# B4L_UI.net
KiCad netlist of a schematic drawn in EAGLE
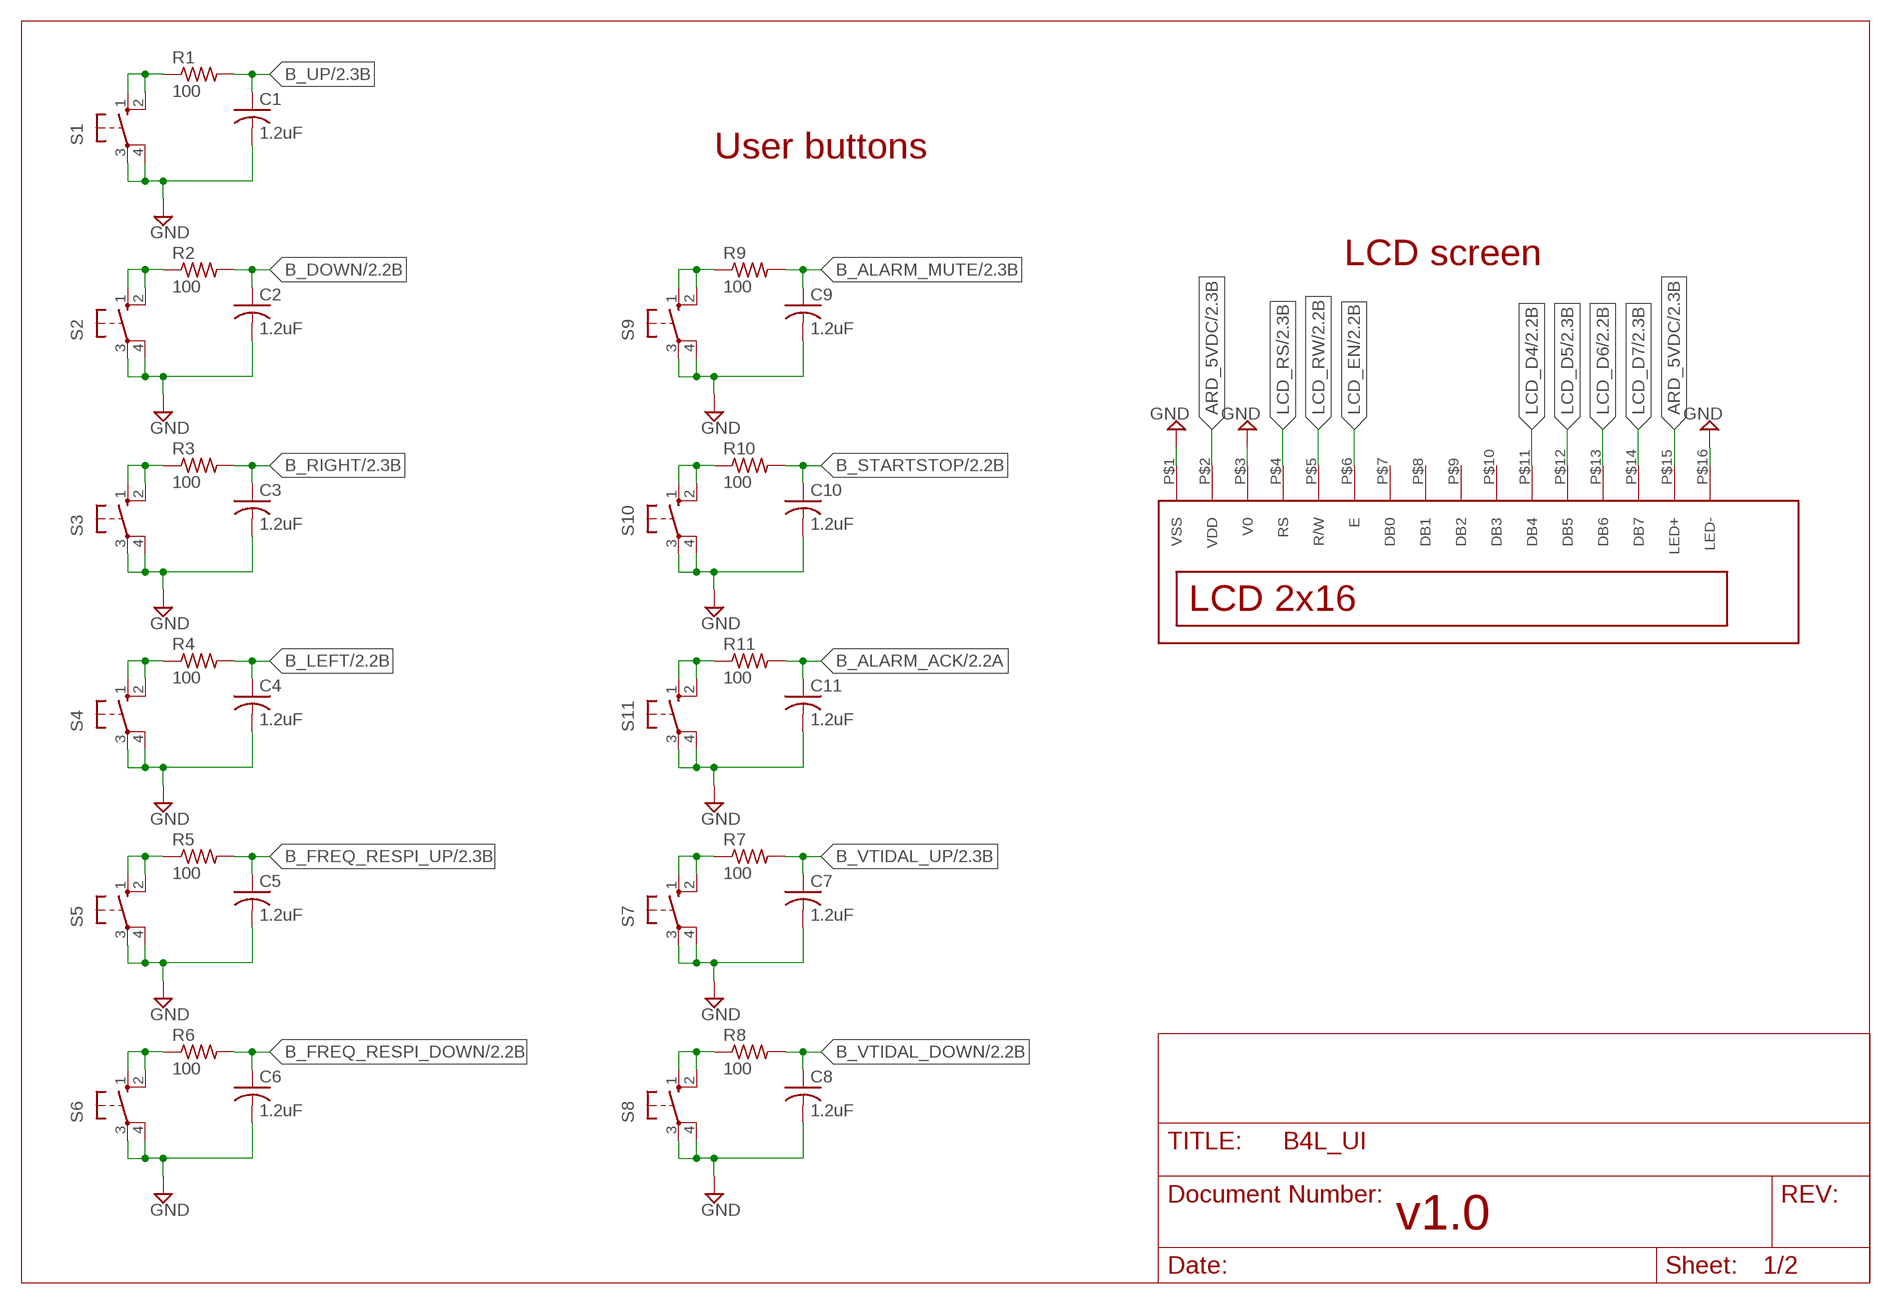
[diagram p0: schematic, sheet 1]
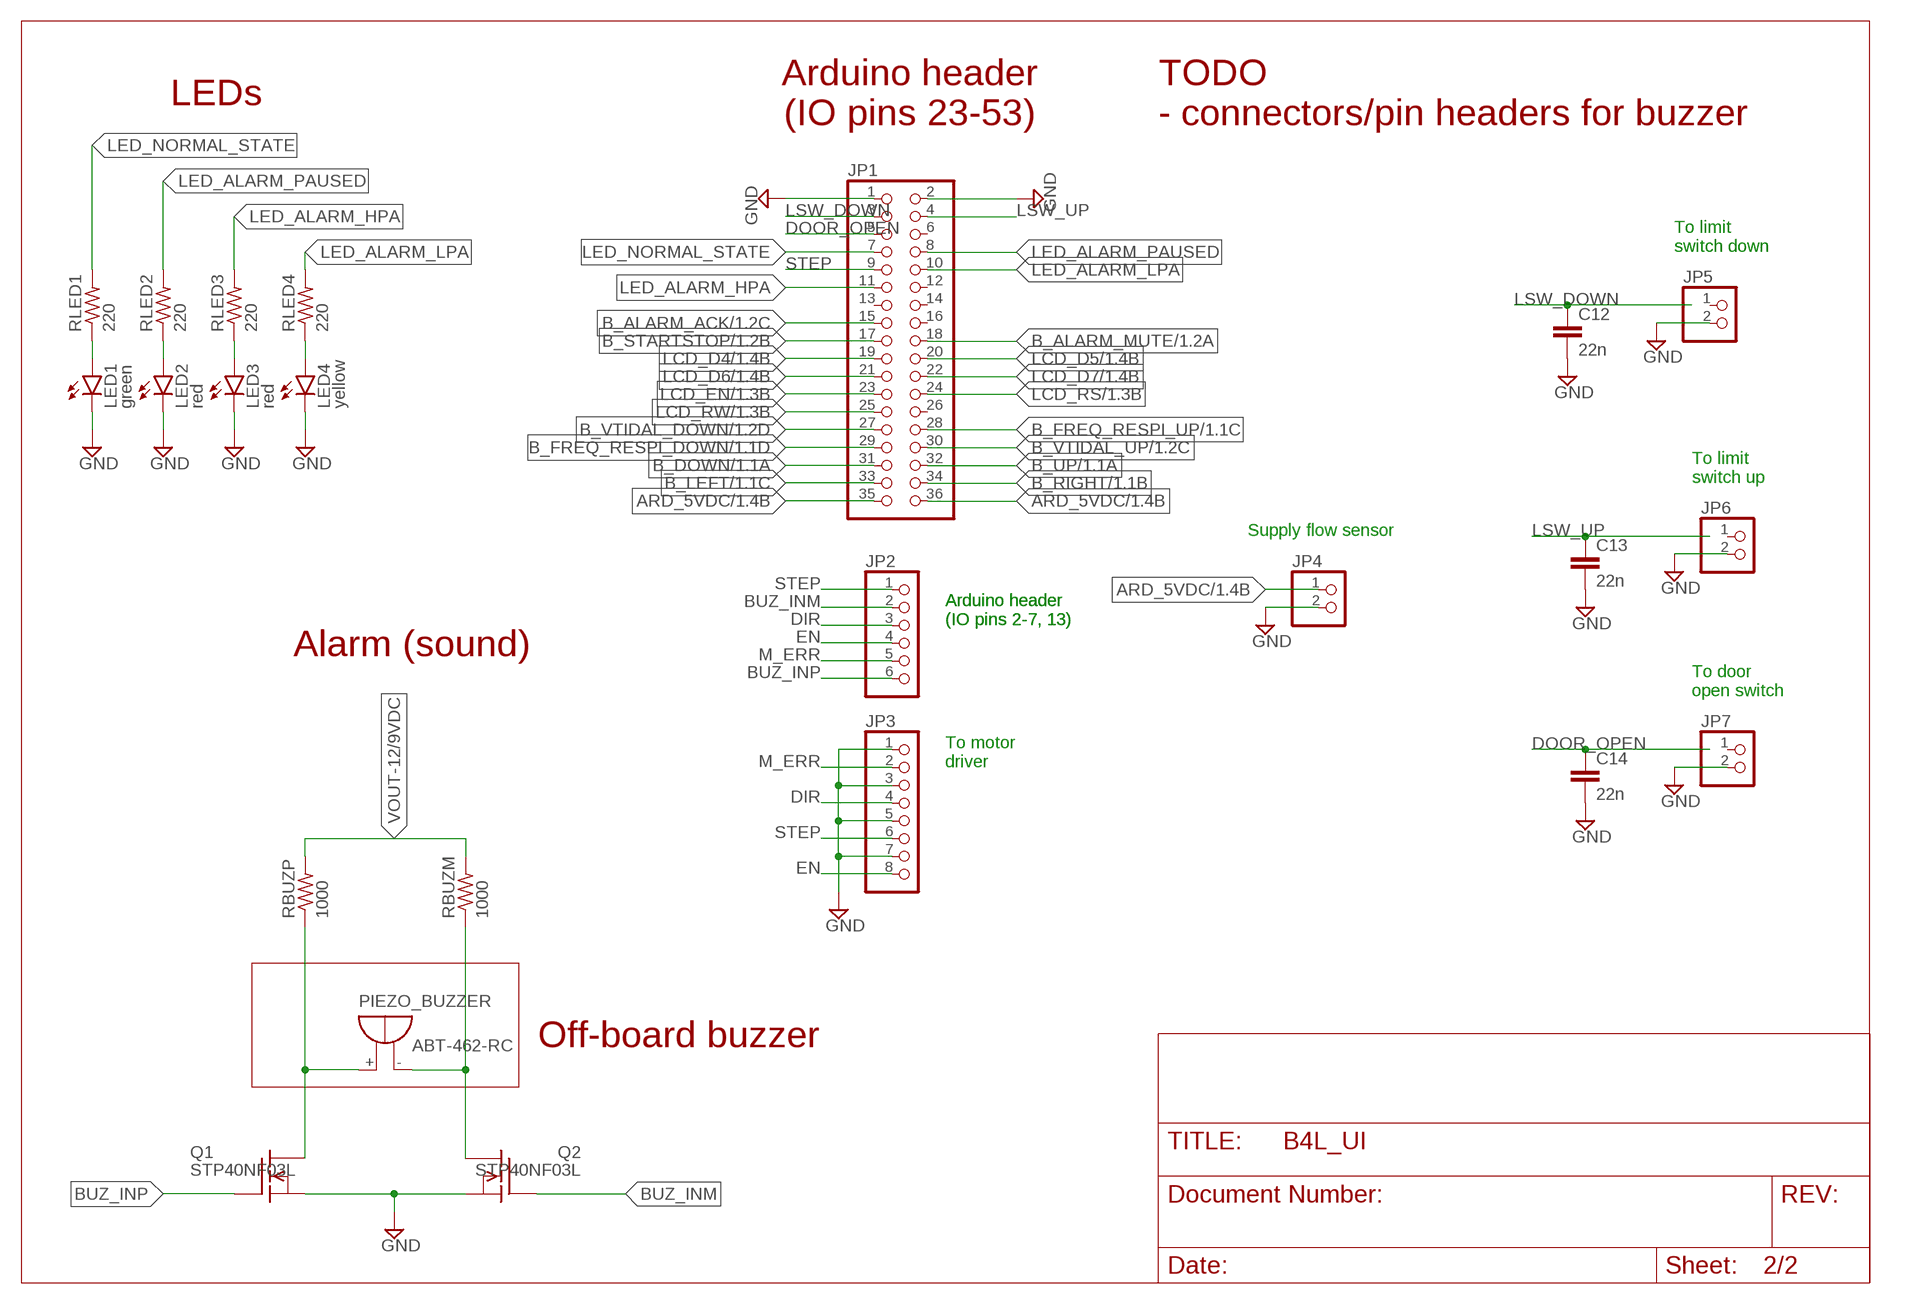
[diagram p1: schematic, sheet 2]

(export (version "E")
  (design (tool "Eeschema 10.0.6"))
  (components
    (comp (ref "C1")
      (value "1.2uF")
      (footprint "eagle-import:C050-050X075")
      (libsource (lib "eagle-import") (part "C-US050-050X075"))
    )
    (comp (ref "C2")
      (value "1.2uF")
      (footprint "eagle-import:C050-050X075")
      (libsource (lib "eagle-import") (part "C-US050-050X075"))
    )
    (comp (ref "C3")
      (value "1.2uF")
      (footprint "eagle-import:C050-050X075")
      (libsource (lib "eagle-import") (part "C-US050-050X075"))
    )
    (comp (ref "C4")
      (value "1.2uF")
      (footprint "eagle-import:C050-050X075")
      (libsource (lib "eagle-import") (part "C-US050-050X075"))
    )
    (comp (ref "C5")
      (value "1.2uF")
      (footprint "eagle-import:C050-050X075")
      (libsource (lib "eagle-import") (part "C-US050-050X075"))
    )
    (comp (ref "C6")
      (value "1.2uF")
      (footprint "eagle-import:C050-050X075")
      (libsource (lib "eagle-import") (part "C-US050-050X075"))
    )
    (comp (ref "C7")
      (value "1.2uF")
      (footprint "eagle-import:C050-050X075")
      (libsource (lib "eagle-import") (part "C-US050-050X075"))
    )
    (comp (ref "C8")
      (value "1.2uF")
      (footprint "eagle-import:C050-050X075")
      (libsource (lib "eagle-import") (part "C-US050-050X075"))
    )
    (comp (ref "C9")
      (value "1.2uF")
      (footprint "eagle-import:C050-050X075")
      (libsource (lib "eagle-import") (part "C-US050-050X075"))
    )
    (comp (ref "C10")
      (value "1.2uF")
      (footprint "eagle-import:C050-050X075")
      (libsource (lib "eagle-import") (part "C-US050-050X075"))
    )
    (comp (ref "C11")
      (value "1.2uF")
      (footprint "eagle-import:C050-050X075")
      (libsource (lib "eagle-import") (part "C-US050-050X075"))
    )
    (comp (ref "R1")
      (value "100")
      (footprint "eagle-import:0309_12")
      (libsource (lib "eagle-import") (part "R-US_0309/12"))
    )
    (comp (ref "R2")
      (value "100")
      (footprint "eagle-import:0309_12")
      (libsource (lib "eagle-import") (part "R-US_0309/12"))
    )
    (comp (ref "R3")
      (value "100")
      (footprint "eagle-import:0309_12")
      (libsource (lib "eagle-import") (part "R-US_0309/12"))
    )
    (comp (ref "R4")
      (value "100")
      (footprint "eagle-import:0309_12")
      (libsource (lib "eagle-import") (part "R-US_0309/12"))
    )
    (comp (ref "R5")
      (value "100")
      (footprint "eagle-import:0309_12")
      (libsource (lib "eagle-import") (part "R-US_0309/12"))
    )
    (comp (ref "R6")
      (value "100")
      (footprint "eagle-import:0309_12")
      (libsource (lib "eagle-import") (part "R-US_0309/12"))
    )
    (comp (ref "R7")
      (value "100")
      (footprint "eagle-import:0309_12")
      (libsource (lib "eagle-import") (part "R-US_0309/12"))
    )
    (comp (ref "R8")
      (value "100")
      (footprint "eagle-import:0309_12")
      (libsource (lib "eagle-import") (part "R-US_0309/12"))
    )
    (comp (ref "R9")
      (value "100")
      (footprint "eagle-import:0309_12")
      (libsource (lib "eagle-import") (part "R-US_0309/12"))
    )
    (comp (ref "R10")
      (value "100")
      (footprint "eagle-import:0309_12")
      (libsource (lib "eagle-import") (part "R-US_0309/12"))
    )
    (comp (ref "R11")
      (value "100")
      (footprint "eagle-import:0309_12")
      (libsource (lib "eagle-import") (part "R-US_0309/12"))
    )
    (comp (ref "S1")
      (value "40-XX")
      (footprint "eagle-import:B3F-40XX")
      (fields (field (name "MF") "OMRON COMPONENTS USA") (field (name "MPN") "B3F-4000"))
      (libsource (lib "eagle-import") (part "40-XX"))
    )
    (comp (ref "S2")
      (value "40-XX")
      (footprint "eagle-import:B3F-40XX")
      (fields (field (name "MF") "OMRON COMPONENTS USA") (field (name "MPN") "B3F-4000"))
      (libsource (lib "eagle-import") (part "40-XX"))
    )
    (comp (ref "S3")
      (value "40-XX")
      (footprint "eagle-import:B3F-40XX")
      (fields (field (name "MF") "OMRON COMPONENTS USA") (field (name "MPN") "B3F-4000"))
      (libsource (lib "eagle-import") (part "40-XX"))
    )
    (comp (ref "S4")
      (value "40-XX")
      (footprint "eagle-import:B3F-40XX")
      (fields (field (name "MF") "OMRON COMPONENTS USA") (field (name "MPN") "B3F-4000"))
      (libsource (lib "eagle-import") (part "40-XX"))
    )
    (comp (ref "S5")
      (value "40-XX")
      (footprint "eagle-import:B3F-40XX")
      (fields (field (name "MF") "OMRON COMPONENTS USA") (field (name "MPN") "B3F-4000"))
      (libsource (lib "eagle-import") (part "40-XX"))
    )
    (comp (ref "S6")
      (value "40-XX")
      (footprint "eagle-import:B3F-40XX")
      (fields (field (name "MF") "OMRON COMPONENTS USA") (field (name "MPN") "B3F-4000"))
      (libsource (lib "eagle-import") (part "40-XX"))
    )
    (comp (ref "S7")
      (value "40-XX")
      (footprint "eagle-import:B3F-40XX")
      (fields (field (name "MF") "OMRON COMPONENTS USA") (field (name "MPN") "B3F-4000"))
      (libsource (lib "eagle-import") (part "40-XX"))
    )
    (comp (ref "S8")
      (value "40-XX")
      (footprint "eagle-import:B3F-40XX")
      (fields (field (name "MF") "OMRON COMPONENTS USA") (field (name "MPN") "B3F-4000"))
      (libsource (lib "eagle-import") (part "40-XX"))
    )
    (comp (ref "S9")
      (value "40-XX")
      (footprint "eagle-import:B3F-40XX")
      (fields (field (name "MF") "OMRON COMPONENTS USA") (field (name "MPN") "B3F-4000"))
      (libsource (lib "eagle-import") (part "40-XX"))
    )
    (comp (ref "S10")
      (value "40-XX")
      (footprint "eagle-import:B3F-40XX")
      (fields (field (name "MF") "OMRON COMPONENTS USA") (field (name "MPN") "B3F-4000"))
      (libsource (lib "eagle-import") (part "40-XX"))
    )
    (comp (ref "S11")
      (value "40-XX")
      (footprint "eagle-import:B3F-40XX")
      (fields (field (name "MF") "OMRON COMPONENTS USA") (field (name "MPN") "B3F-4000"))
      (libsource (lib "eagle-import") (part "40-XX"))
    )
    (comp (ref "U$1")
      (value "LCD_MC21605C6W-BNMLW-V2")
      (footprint "eagle-import:LCD_MC21605C6W-BNMLW-V2")
      (libsource (lib "eagle-import") (part "LCD_MC21605C6W-BNMLW-V2"))
    )
    (comp (ref "C12")
      (value "22n")
      (footprint "eagle-import:C2.5-3")
      (libsource (lib "eagle-import") (part "C2,5-3"))
    )
    (comp (ref "C13")
      (value "22n")
      (footprint "eagle-import:C2.5-3")
      (libsource (lib "eagle-import") (part "C2,5-3"))
    )
    (comp (ref "C14")
      (value "22n")
      (footprint "eagle-import:C2.5-3")
      (libsource (lib "eagle-import") (part "C2,5-3"))
    )
    (comp (ref "JP1")
      (value "PINHD-2X18")
      (footprint "eagle-import:2X18")
      (libsource (lib "eagle-import") (part "PINHD-2X18"))
    )
    (comp (ref "JP2")
      (value "PINHD-1X6")
      (footprint "eagle-import:1X06")
      (libsource (lib "eagle-import") (part "PINHD-1X6"))
    )
    (comp (ref "JP3")
      (value "PINHD-1X8")
      (footprint "eagle-import:1X08")
      (libsource (lib "eagle-import") (part "PINHD-1X8"))
    )
    (comp (ref "JP4")
      (value "PINHD-1X2")
      (footprint "eagle-import:1X02")
      (libsource (lib "eagle-import") (part "PINHD-1X2"))
    )
    (comp (ref "JP5")
      (value "PINHD-1X2")
      (footprint "eagle-import:1X02")
      (libsource (lib "eagle-import") (part "PINHD-1X2"))
    )
    (comp (ref "JP6")
      (value "PINHD-1X2")
      (footprint "eagle-import:1X02")
      (libsource (lib "eagle-import") (part "PINHD-1X2"))
    )
    (comp (ref "JP7")
      (value "PINHD-1X2")
      (footprint "eagle-import:1X02")
      (libsource (lib "eagle-import") (part "PINHD-1X2"))
    )
    (comp (ref "LED1")
      (value "green")
      (footprint "eagle-import:LED5MM")
      (libsource (lib "eagle-import") (part "LED5MM"))
    )
    (comp (ref "LED2")
      (value "red")
      (footprint "eagle-import:LED5MM")
      (libsource (lib "eagle-import") (part "LED5MM"))
    )
    (comp (ref "LED3")
      (value "red")
      (footprint "eagle-import:LED5MM")
      (libsource (lib "eagle-import") (part "LED5MM"))
    )
    (comp (ref "LED4")
      (value "yellow")
      (footprint "eagle-import:LED5MM")
      (libsource (lib "eagle-import") (part "LED5MM"))
    )
    (comp (ref "PIEZO_BUZZER")
      (value "ABT-462-RC")
      (footprint "eagle-import:F_TMB")
      (libsource (lib "eagle-import") (part "F/TMB"))
    )
    (comp (ref "Q1")
      (value "STP40NF03L")
      (footprint "eagle-import:TO220")
      (libsource (lib "eagle-import") (part "BUZ10"))
    )
    (comp (ref "Q2")
      (value "STP40NF03L")
      (footprint "eagle-import:TO220")
      (libsource (lib "eagle-import") (part "BUZ10"))
    )
    (comp (ref "RBUZM")
      (value "1000")
      (footprint "eagle-import:0309_12")
      (libsource (lib "eagle-import") (part "R-US_0309/12"))
    )
    (comp (ref "RBUZP")
      (value "1000")
      (footprint "eagle-import:0309_12")
      (libsource (lib "eagle-import") (part "R-US_0309/12"))
    )
    (comp (ref "RLED1")
      (value "220")
      (footprint "eagle-import:0309_12")
      (libsource (lib "eagle-import") (part "R-US_0309/12"))
    )
    (comp (ref "RLED2")
      (value "220")
      (footprint "eagle-import:0309_12")
      (libsource (lib "eagle-import") (part "R-US_0309/12"))
    )
    (comp (ref "RLED3")
      (value "220")
      (footprint "eagle-import:0309_12")
      (libsource (lib "eagle-import") (part "R-US_0309/12"))
    )
    (comp (ref "RLED4")
      (value "220")
      (footprint "eagle-import:0309_12")
      (libsource (lib "eagle-import") (part "R-US_0309/12"))
    )
  )
  (nets
    (net (code "1") (name "ARD_5VDC") (class "Default")
      (node (ref "JP1") (pin "35") (pinfunction "35_35") (pintype "passive"))
      (node (ref "JP1") (pin "36") (pinfunction "36_36") (pintype "passive"))
      (node (ref "U$1") (pin "P$15") (pinfunction "LED+_P$15") (pintype "bidirectional"))
      (node (ref "U$1") (pin "P$2") (pinfunction "VDD_P$2") (pintype "bidirectional"))
    )
    (net (code "2") (name "BUZ_INM") (class "Default")
      (node (ref "JP2") (pin "2") (pinfunction "2_2") (pintype "passive"))
      (node (ref "Q2") (pin "1") (pinfunction "G_1") (pintype "passive"))
    )
    (net (code "3") (name "BUZ_INP") (class "Default")
      (node (ref "JP2") (pin "6") (pinfunction "6_6") (pintype "passive"))
      (node (ref "Q1") (pin "1") (pinfunction "G_1") (pintype "passive"))
    )
    (net (code "4") (name "B_ALARM_ACK") (class "Default")
      (node (ref "C11") (pin "1") (pinfunction "1_1") (pintype "passive"))
      (node (ref "JP1") (pin "15") (pinfunction "15_15") (pintype "passive"))
      (node (ref "R11") (pin "2") (pinfunction "2_2") (pintype "passive"))
    )
    (net (code "5") (name "B_ALARM_MUTE") (class "Default")
      (node (ref "C9") (pin "1") (pinfunction "1_1") (pintype "passive"))
      (node (ref "JP1") (pin "18") (pinfunction "18_18") (pintype "passive"))
      (node (ref "R9") (pin "2") (pinfunction "2_2") (pintype "passive"))
    )
    (net (code "6") (name "B_DOWN") (class "Default")
      (node (ref "C2") (pin "1") (pinfunction "1_1") (pintype "passive"))
      (node (ref "JP1") (pin "31") (pinfunction "31_31") (pintype "passive"))
      (node (ref "R2") (pin "2") (pinfunction "2_2") (pintype "passive"))
    )
    (net (code "7") (name "B_FREQ_RESPI_DOWN") (class "Default")
      (node (ref "C6") (pin "1") (pinfunction "1_1") (pintype "passive"))
      (node (ref "JP1") (pin "29") (pinfunction "29_29") (pintype "passive"))
      (node (ref "R6") (pin "2") (pinfunction "2_2") (pintype "passive"))
    )
    (net (code "8") (name "B_FREQ_RESPI_UP") (class "Default")
      (node (ref "C5") (pin "1") (pinfunction "1_1") (pintype "passive"))
      (node (ref "JP1") (pin "28") (pinfunction "28_28") (pintype "passive"))
      (node (ref "R5") (pin "2") (pinfunction "2_2") (pintype "passive"))
    )
    (net (code "9") (name "B_LEFT") (class "Default")
      (node (ref "C4") (pin "1") (pinfunction "1_1") (pintype "passive"))
      (node (ref "JP1") (pin "33") (pinfunction "33_33") (pintype "passive"))
      (node (ref "R4") (pin "2") (pinfunction "2_2") (pintype "passive"))
    )
    (net (code "10") (name "B_RIGHT") (class "Default")
      (node (ref "C3") (pin "1") (pinfunction "1_1") (pintype "passive"))
      (node (ref "JP1") (pin "34") (pinfunction "34_34") (pintype "passive"))
      (node (ref "R3") (pin "2") (pinfunction "2_2") (pintype "passive"))
    )
    (net (code "11") (name "B_STARTSTOP") (class "Default")
      (node (ref "C10") (pin "1") (pinfunction "1_1") (pintype "passive"))
      (node (ref "JP1") (pin "17") (pinfunction "17_17") (pintype "passive"))
      (node (ref "R10") (pin "2") (pinfunction "2_2") (pintype "passive"))
    )
    (net (code "12") (name "B_UP") (class "Default")
      (node (ref "C1") (pin "1") (pinfunction "1_1") (pintype "passive"))
      (node (ref "JP1") (pin "32") (pinfunction "32_32") (pintype "passive"))
      (node (ref "R1") (pin "2") (pinfunction "2_2") (pintype "passive"))
    )
    (net (code "13") (name "B_VTIDAL_DOWN") (class "Default")
      (node (ref "C8") (pin "1") (pinfunction "1_1") (pintype "passive"))
      (node (ref "JP1") (pin "27") (pinfunction "27_27") (pintype "passive"))
      (node (ref "R8") (pin "2") (pinfunction "2_2") (pintype "passive"))
    )
    (net (code "14") (name "B_VTIDAL_UP") (class "Default")
      (node (ref "C7") (pin "1") (pinfunction "1_1") (pintype "passive"))
      (node (ref "JP1") (pin "30") (pinfunction "30_30") (pintype "passive"))
      (node (ref "R7") (pin "2") (pinfunction "2_2") (pintype "passive"))
    )
    (net (code "15") (name "DIR") (class "Default")
      (node (ref "JP2") (pin "3") (pinfunction "3_3") (pintype "passive"))
      (node (ref "JP3") (pin "4") (pinfunction "4_4") (pintype "passive"))
    )
    (net (code "16") (name "DOOR_OPEN") (class "Default")
      (node (ref "C14") (pin "1") (pinfunction "1_1") (pintype "passive"))
      (node (ref "JP1") (pin "5") (pinfunction "5_5") (pintype "passive"))
    )
    (net (code "17") (name "EN") (class "Default")
      (node (ref "JP2") (pin "4") (pinfunction "4_4") (pintype "passive"))
      (node (ref "JP3") (pin "8") (pinfunction "8_8") (pintype "passive"))
    )
    (net (code "18") (name "GND") (class "Default")
      (node (ref "C1") (pin "2") (pinfunction "2_2") (pintype "passive"))
      (node (ref "C10") (pin "2") (pinfunction "2_2") (pintype "passive"))
      (node (ref "C11") (pin "2") (pinfunction "2_2") (pintype "passive"))
      (node (ref "C12") (pin "2") (pinfunction "2_2") (pintype "passive"))
      (node (ref "C13") (pin "2") (pinfunction "2_2") (pintype "passive"))
      (node (ref "C14") (pin "2") (pinfunction "2_2") (pintype "passive"))
      (node (ref "C2") (pin "2") (pinfunction "2_2") (pintype "passive"))
      (node (ref "C3") (pin "2") (pinfunction "2_2") (pintype "passive"))
      (node (ref "C4") (pin "2") (pinfunction "2_2") (pintype "passive"))
      (node (ref "C5") (pin "2") (pinfunction "2_2") (pintype "passive"))
      (node (ref "C6") (pin "2") (pinfunction "2_2") (pintype "passive"))
      (node (ref "C7") (pin "2") (pinfunction "2_2") (pintype "passive"))
      (node (ref "C8") (pin "2") (pinfunction "2_2") (pintype "passive"))
      (node (ref "C9") (pin "2") (pinfunction "2_2") (pintype "passive"))
      (node (ref "JP1") (pin "1") (pinfunction "1_1") (pintype "passive"))
      (node (ref "JP1") (pin "2") (pinfunction "2_2") (pintype "passive"))
      (node (ref "JP3") (pin "1") (pinfunction "1_1") (pintype "passive"))
      (node (ref "JP3") (pin "3") (pinfunction "3_3") (pintype "passive"))
      (node (ref "JP3") (pin "5") (pinfunction "5_5") (pintype "passive"))
      (node (ref "JP3") (pin "7") (pinfunction "7_7") (pintype "passive"))
      (node (ref "JP4") (pin "2") (pinfunction "2_2") (pintype "passive"))
      (node (ref "JP5") (pin "2") (pinfunction "2_2") (pintype "passive"))
      (node (ref "JP6") (pin "2") (pinfunction "2_2") (pintype "passive"))
      (node (ref "JP7") (pin "2") (pinfunction "2_2") (pintype "passive"))
      (node (ref "LED1") (pin "K") (pinfunction "C_K") (pintype "passive"))
      (node (ref "LED2") (pin "K") (pinfunction "C_K") (pintype "passive"))
      (node (ref "LED3") (pin "K") (pinfunction "C_K") (pintype "passive"))
      (node (ref "LED4") (pin "K") (pinfunction "C_K") (pintype "passive"))
      (node (ref "Q1") (pin "3") (pinfunction "S_3") (pintype "passive"))
      (node (ref "Q2") (pin "3") (pinfunction "S_3") (pintype "passive"))
      (node (ref "S1") (pin "3") (pinfunction "P_3") (pintype "passive"))
      (node (ref "S1") (pin "4") (pinfunction "P1_4") (pintype "passive"))
      (node (ref "S10") (pin "3") (pinfunction "P_3") (pintype "passive"))
      (node (ref "S10") (pin "4") (pinfunction "P1_4") (pintype "passive"))
      (node (ref "S11") (pin "3") (pinfunction "P_3") (pintype "passive"))
      (node (ref "S11") (pin "4") (pinfunction "P1_4") (pintype "passive"))
      (node (ref "S2") (pin "3") (pinfunction "P_3") (pintype "passive"))
      (node (ref "S2") (pin "4") (pinfunction "P1_4") (pintype "passive"))
      (node (ref "S3") (pin "3") (pinfunction "P_3") (pintype "passive"))
      (node (ref "S3") (pin "4") (pinfunction "P1_4") (pintype "passive"))
      (node (ref "S4") (pin "3") (pinfunction "P_3") (pintype "passive"))
      (node (ref "S4") (pin "4") (pinfunction "P1_4") (pintype "passive"))
      (node (ref "S5") (pin "3") (pinfunction "P_3") (pintype "passive"))
      (node (ref "S5") (pin "4") (pinfunction "P1_4") (pintype "passive"))
      (node (ref "S6") (pin "3") (pinfunction "P_3") (pintype "passive"))
      (node (ref "S6") (pin "4") (pinfunction "P1_4") (pintype "passive"))
      (node (ref "S7") (pin "3") (pinfunction "P_3") (pintype "passive"))
      (node (ref "S7") (pin "4") (pinfunction "P1_4") (pintype "passive"))
      (node (ref "S8") (pin "3") (pinfunction "P_3") (pintype "passive"))
      (node (ref "S8") (pin "4") (pinfunction "P1_4") (pintype "passive"))
      (node (ref "S9") (pin "3") (pinfunction "P_3") (pintype "passive"))
      (node (ref "S9") (pin "4") (pinfunction "P1_4") (pintype "passive"))
      (node (ref "U$1") (pin "P$1") (pinfunction "VSS_P$1") (pintype "bidirectional"))
      (node (ref "U$1") (pin "P$16") (pinfunction "LED-_P$16") (pintype "bidirectional"))
      (node (ref "U$1") (pin "P$3") (pinfunction "V0_P$3") (pintype "bidirectional"))
    )
    (net (code "19") (name "LCD_D4") (class "Default")
      (node (ref "JP1") (pin "19") (pinfunction "19_19") (pintype "passive"))
      (node (ref "U$1") (pin "P$11") (pinfunction "DB4_P$11") (pintype "bidirectional"))
    )
    (net (code "20") (name "LCD_D5") (class "Default")
      (node (ref "JP1") (pin "20") (pinfunction "20_20") (pintype "passive"))
      (node (ref "U$1") (pin "P$12") (pinfunction "DB5_P$12") (pintype "bidirectional"))
    )
    (net (code "21") (name "LCD_D6") (class "Default")
      (node (ref "JP1") (pin "21") (pinfunction "21_21") (pintype "passive"))
      (node (ref "U$1") (pin "P$13") (pinfunction "DB6_P$13") (pintype "bidirectional"))
    )
    (net (code "22") (name "LCD_D7") (class "Default")
      (node (ref "JP1") (pin "22") (pinfunction "22_22") (pintype "passive"))
      (node (ref "U$1") (pin "P$14") (pinfunction "DB7_P$14") (pintype "bidirectional"))
    )
    (net (code "23") (name "LCD_EN") (class "Default")
      (node (ref "JP1") (pin "23") (pinfunction "23_23") (pintype "passive"))
      (node (ref "U$1") (pin "P$6") (pinfunction "E_P$6") (pintype "bidirectional"))
    )
    (net (code "24") (name "LCD_RS") (class "Default")
      (node (ref "JP1") (pin "24") (pinfunction "24_24") (pintype "passive"))
      (node (ref "U$1") (pin "P$4") (pinfunction "RS_P$4") (pintype "bidirectional"))
    )
    (net (code "25") (name "LCD_RW") (class "Default")
      (node (ref "JP1") (pin "25") (pinfunction "25_25") (pintype "passive"))
      (node (ref "U$1") (pin "P$5") (pinfunction "R/W_P$5") (pintype "bidirectional"))
    )
    (net (code "26") (name "LED_ALARM_HPA") (class "Default")
      (node (ref "JP1") (pin "11") (pinfunction "11_11") (pintype "passive"))
      (node (ref "RLED3") (pin "2") (pinfunction "2_2") (pintype "passive"))
    )
    (net (code "27") (name "LED_ALARM_LPA") (class "Default")
      (node (ref "JP1") (pin "10") (pinfunction "10_10") (pintype "passive"))
      (node (ref "RLED4") (pin "2") (pinfunction "2_2") (pintype "passive"))
    )
    (net (code "28") (name "LED_ALARM_PAUSED") (class "Default")
      (node (ref "JP1") (pin "8") (pinfunction "8_8") (pintype "passive"))
      (node (ref "RLED2") (pin "2") (pinfunction "2_2") (pintype "passive"))
    )
    (net (code "29") (name "LED_NORMAL_STATE") (class "Default")
      (node (ref "JP1") (pin "7") (pinfunction "7_7") (pintype "passive"))
      (node (ref "RLED1") (pin "2") (pinfunction "2_2") (pintype "passive"))
    )
    (net (code "30") (name "LSW_DOWN") (class "Default")
      (node (ref "C12") (pin "1") (pinfunction "1_1") (pintype "passive"))
      (node (ref "JP1") (pin "3") (pinfunction "3_3") (pintype "passive"))
    )
    (net (code "31") (name "LSW_UP") (class "Default")
      (node (ref "C13") (pin "1") (pinfunction "1_1") (pintype "passive"))
      (node (ref "JP1") (pin "4") (pinfunction "4_4") (pintype "passive"))
    )
    (net (code "32") (name "M_ERR") (class "Default")
      (node (ref "JP2") (pin "5") (pinfunction "5_5") (pintype "passive"))
      (node (ref "JP3") (pin "2") (pinfunction "2_2") (pintype "passive"))
    )
    (net (code "33") (name "Net-(LED1-PadA)") (class "Default")
      (node (ref "LED1") (pin "A") (pinfunction "A_A") (pintype "passive"))
      (node (ref "RLED1") (pin "1") (pinfunction "1_1") (pintype "passive"))
    )
    (net (code "34") (name "Net-(LED2-PadA)") (class "Default")
      (node (ref "LED2") (pin "A") (pinfunction "A_A") (pintype "passive"))
      (node (ref "RLED2") (pin "1") (pinfunction "1_1") (pintype "passive"))
    )
    (net (code "35") (name "Net-(LED3-PadA)") (class "Default")
      (node (ref "LED3") (pin "A") (pinfunction "A_A") (pintype "passive"))
      (node (ref "RLED3") (pin "1") (pinfunction "1_1") (pintype "passive"))
    )
    (net (code "36") (name "Net-(LED4-PadA)") (class "Default")
      (node (ref "LED4") (pin "A") (pinfunction "A_A") (pintype "passive"))
      (node (ref "RLED4") (pin "1") (pinfunction "1_1") (pintype "passive"))
    )
    (net (code "37") (name "Net-(Q1-D)") (class "Default")
      (node (ref "PIEZO_BUZZER") (pin "+") (pinfunction "+_+") (pintype "passive"))
      (node (ref "Q1") (pin "2") (pinfunction "D_2") (pintype "passive"))
      (node (ref "RBUZP") (pin "1") (pinfunction "1_1") (pintype "passive"))
    )
    (net (code "38") (name "Net-(Q2-D)") (class "Default")
      (node (ref "PIEZO_BUZZER") (pin "-") (pinfunction "-_-") (pintype "passive"))
      (node (ref "Q2") (pin "2") (pinfunction "D_2") (pintype "passive"))
      (node (ref "RBUZM") (pin "1") (pinfunction "1_1") (pintype "passive"))
    )
    (net (code "39") (name "Net-(S1-S)") (class "Default")
      (node (ref "R1") (pin "1") (pinfunction "1_1") (pintype "passive"))
      (node (ref "S1") (pin "1") (pinfunction "S_1") (pintype "passive"))
      (node (ref "S1") (pin "2") (pinfunction "S1_2") (pintype "passive"))
    )
    (net (code "40") (name "Net-(S2-S)") (class "Default")
      (node (ref "R2") (pin "1") (pinfunction "1_1") (pintype "passive"))
      (node (ref "S2") (pin "1") (pinfunction "S_1") (pintype "passive"))
      (node (ref "S2") (pin "2") (pinfunction "S1_2") (pintype "passive"))
    )
    (net (code "41") (name "Net-(S3-S)") (class "Default")
      (node (ref "R3") (pin "1") (pinfunction "1_1") (pintype "passive"))
      (node (ref "S3") (pin "1") (pinfunction "S_1") (pintype "passive"))
      (node (ref "S3") (pin "2") (pinfunction "S1_2") (pintype "passive"))
    )
    (net (code "42") (name "Net-(S4-S)") (class "Default")
      (node (ref "R4") (pin "1") (pinfunction "1_1") (pintype "passive"))
      (node (ref "S4") (pin "1") (pinfunction "S_1") (pintype "passive"))
      (node (ref "S4") (pin "2") (pinfunction "S1_2") (pintype "passive"))
    )
    (net (code "43") (name "Net-(S5-S)") (class "Default")
      (node (ref "R5") (pin "1") (pinfunction "1_1") (pintype "passive"))
      (node (ref "S5") (pin "1") (pinfunction "S_1") (pintype "passive"))
      (node (ref "S5") (pin "2") (pinfunction "S1_2") (pintype "passive"))
    )
    (net (code "44") (name "Net-(S6-S)") (class "Default")
      (node (ref "R6") (pin "1") (pinfunction "1_1") (pintype "passive"))
      (node (ref "S6") (pin "1") (pinfunction "S_1") (pintype "passive"))
      (node (ref "S6") (pin "2") (pinfunction "S1_2") (pintype "passive"))
    )
    (net (code "45") (name "Net-(S7-S)") (class "Default")
      (node (ref "R7") (pin "1") (pinfunction "1_1") (pintype "passive"))
      (node (ref "S7") (pin "1") (pinfunction "S_1") (pintype "passive"))
      (node (ref "S7") (pin "2") (pinfunction "S1_2") (pintype "passive"))
    )
    (net (code "46") (name "Net-(S8-S)") (class "Default")
      (node (ref "R8") (pin "1") (pinfunction "1_1") (pintype "passive"))
      (node (ref "S8") (pin "1") (pinfunction "S_1") (pintype "passive"))
      (node (ref "S8") (pin "2") (pinfunction "S1_2") (pintype "passive"))
    )
    (net (code "47") (name "Net-(S9-S)") (class "Default")
      (node (ref "R9") (pin "1") (pinfunction "1_1") (pintype "passive"))
      (node (ref "S9") (pin "1") (pinfunction "S_1") (pintype "passive"))
      (node (ref "S9") (pin "2") (pinfunction "S1_2") (pintype "passive"))
    )
    (net (code "48") (name "Net-(S10-S)") (class "Default")
      (node (ref "R10") (pin "1") (pinfunction "1_1") (pintype "passive"))
      (node (ref "S10") (pin "1") (pinfunction "S_1") (pintype "passive"))
      (node (ref "S10") (pin "2") (pinfunction "S1_2") (pintype "passive"))
    )
    (net (code "49") (name "Net-(S11-S)") (class "Default")
      (node (ref "R11") (pin "1") (pinfunction "1_1") (pintype "passive"))
      (node (ref "S11") (pin "1") (pinfunction "S_1") (pintype "passive"))
      (node (ref "S11") (pin "2") (pinfunction "S1_2") (pintype "passive"))
    )
    (net (code "50") (name "STEP") (class "Default")
      (node (ref "JP1") (pin "9") (pinfunction "9_9") (pintype "passive"))
      (node (ref "JP2") (pin "1") (pinfunction "1_1") (pintype "passive"))
      (node (ref "JP3") (pin "6") (pinfunction "6_6") (pintype "passive"))
    )
    (net (code "51") (name "VOUT-12{slash}9VDC") (class "Default")
      (node (ref "RBUZM") (pin "2") (pinfunction "2_2") (pintype "passive"))
      (node (ref "RBUZP") (pin "2") (pinfunction "2_2") (pintype "passive"))
    )
    (net (code "52") (name "unconnected-(JP1-Pad6)") (class "Default")
      (node (ref "JP1") (pin "6") (pinfunction "6_6") (pintype "passive"))
    )
    (net (code "53") (name "unconnected-(JP1-Pad12)") (class "Default")
      (node (ref "JP1") (pin "12") (pinfunction "12_12") (pintype "passive"))
    )
    (net (code "54") (name "unconnected-(JP1-Pad13)") (class "Default")
      (node (ref "JP1") (pin "13") (pinfunction "13_13") (pintype "passive"))
    )
    (net (code "55") (name "unconnected-(JP1-Pad14)") (class "Default")
      (node (ref "JP1") (pin "14") (pinfunction "14_14") (pintype "passive"))
    )
    (net (code "56") (name "unconnected-(JP1-Pad16)") (class "Default")
      (node (ref "JP1") (pin "16") (pinfunction "16_16") (pintype "passive"))
    )
    (net (code "57") (name "unconnected-(JP1-Pad26)") (class "Default")
      (node (ref "JP1") (pin "26") (pinfunction "26_26") (pintype "passive"))
    )
    (net (code "58") (name "unconnected-(JP4-Pad1)") (class "Default")
      (node (ref "JP4") (pin "1") (pinfunction "1_1") (pintype "passive"))
    )
    (net (code "59") (name "unconnected-(JP5-Pad1)") (class "Default")
      (node (ref "JP5") (pin "1") (pinfunction "1_1") (pintype "passive"))
    )
    (net (code "60") (name "unconnected-(JP6-Pad1)") (class "Default")
      (node (ref "JP6") (pin "1") (pinfunction "1_1") (pintype "passive"))
    )
    (net (code "61") (name "unconnected-(JP7-Pad1)") (class "Default")
      (node (ref "JP7") (pin "1") (pinfunction "1_1") (pintype "passive"))
    )
    (net (code "62") (name "unconnected-(U$1-DB0-PadP$7)") (class "Default")
      (node (ref "U$1") (pin "P$7") (pinfunction "DB0_P$7") (pintype "bidirectional"))
    )
    (net (code "63") (name "unconnected-(U$1-DB1-PadP$8)") (class "Default")
      (node (ref "U$1") (pin "P$8") (pinfunction "DB1_P$8") (pintype "bidirectional"))
    )
    (net (code "64") (name "unconnected-(U$1-DB2-PadP$9)") (class "Default")
      (node (ref "U$1") (pin "P$9") (pinfunction "DB2_P$9") (pintype "bidirectional"))
    )
    (net (code "65") (name "unconnected-(U$1-DB3-PadP$10)") (class "Default")
      (node (ref "U$1") (pin "P$10") (pinfunction "DB3_P$10") (pintype "bidirectional"))
    )
  )
)
